# Power.net
KiCad netlist of a schematic drawn in Altium Designer
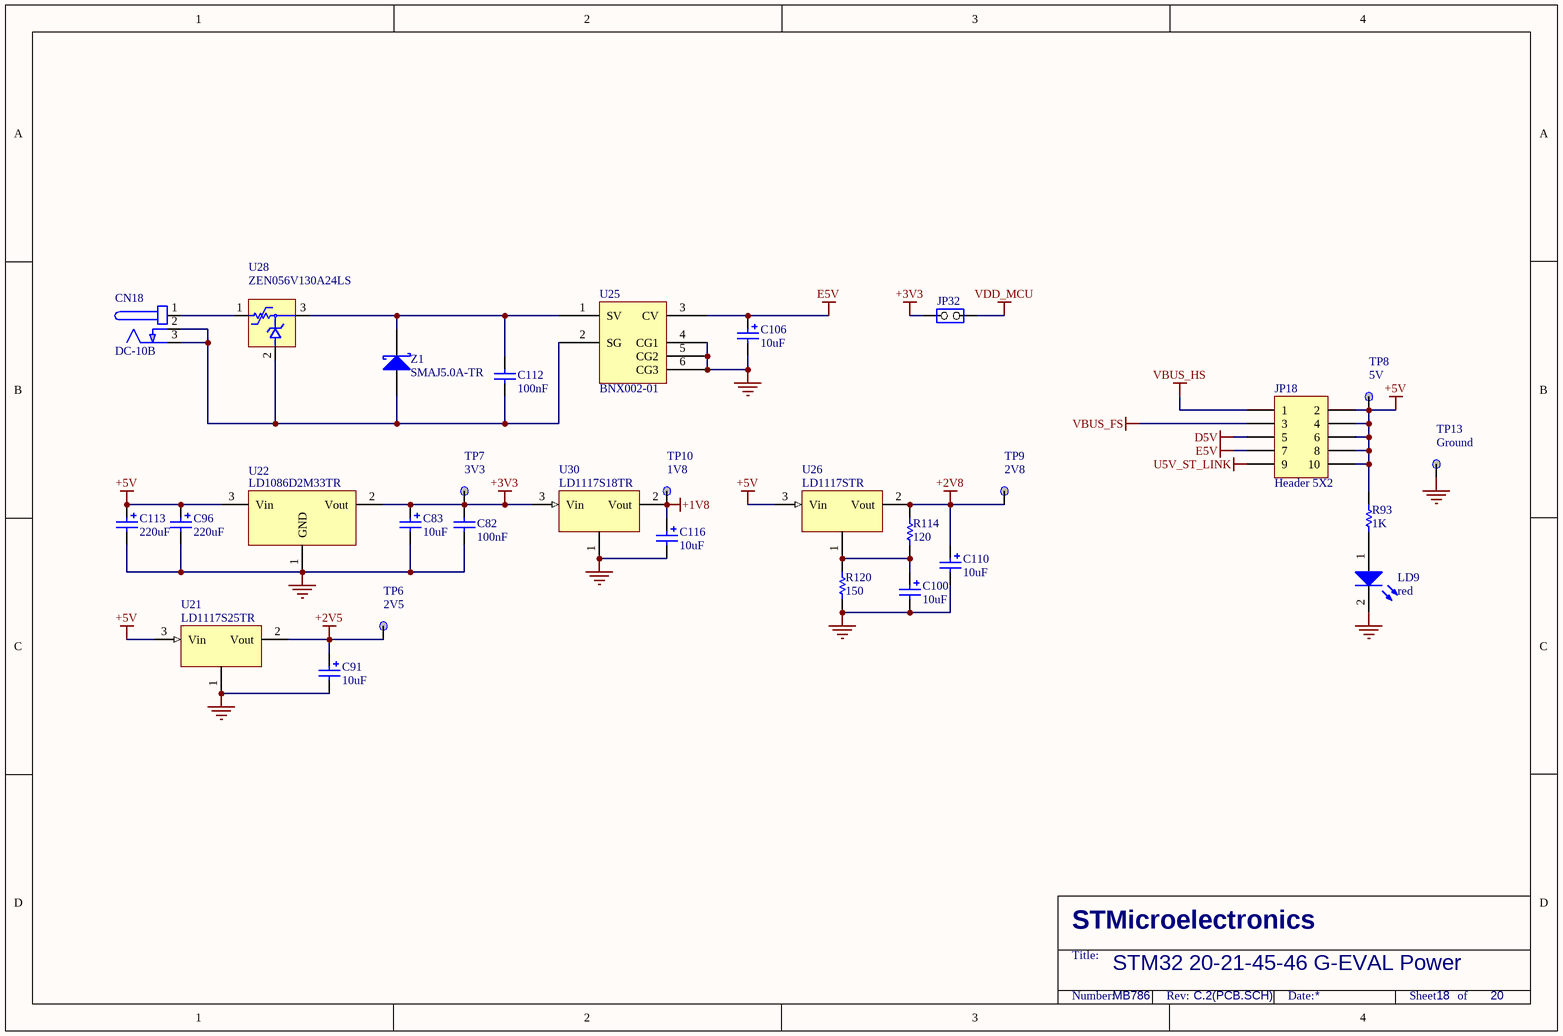
[diagram p0: Power.SchDoc]

(export (version "E")
  (design (tool "Eeschema 10.0.6"))
  (components
    (comp (ref "C82")
      (value "100nF")
      (footprint "0402C")
      (description "Capacitor")
      (fields (field (name "PUBLISHER") "Altium Limited"))
      (libsource (lib "Miscellaneous Devices") (part "Cap"))
    )
    (comp (ref "C83")
      (value "10uF")
      (footprint "TAN-A")
      (description "Polarized Capacitor (Radial)")
      (fields (field (name "PUBLISHER") "Altium Limited"))
      (libsource (lib "Miscellaneous Devices") (part "Cap Pol1"))
    )
    (comp (ref "C91")
      (value "10uF")
      (footprint "TAN-A")
      (description "Polarized Capacitor (Radial)")
      (fields (field (name "PUBLISHER") "Altium Limited"))
      (libsource (lib "Miscellaneous Devices") (part "Cap Pol1"))
    )
    (comp (ref "C96")
      (value "220uF")
      (footprint "C310M-6")
      (description "Polarized Capacitor (Radial)")
      (fields (field (name "PUBLISHER") "Altium Limited"))
      (libsource (lib "Miscellaneous Devices") (part "Cap Pol1"))
    )
    (comp (ref "C100")
      (value "10uF")
      (footprint "TAN-A")
      (description "Polarized Capacitor (Radial)")
      (fields (field (name "PUBLISHER") "Altium Limited"))
      (libsource (lib "Miscellaneous Devices") (part "Cap Pol1"))
    )
    (comp (ref "C106")
      (value "10uF")
      (footprint "C160M-5.5")
      (description "Polarized Capacitor (Radial)")
      (fields (field (name "PUBLISHER") "Altium Limited"))
      (libsource (lib "Miscellaneous Devices") (part "Cap Pol1"))
    )
    (comp (ref "C110")
      (value "10uF")
      (footprint "TAN-A")
      (description "Polarized Capacitor (Radial)")
      (fields (field (name "PUBLISHER") "Altium Limited"))
      (libsource (lib "Miscellaneous Devices") (part "Cap Pol1"))
    )
    (comp (ref "C112")
      (value "100nF")
      (footprint "0402C")
      (description "Capacitor")
      (fields (field (name "PUBLISHER") "Altium Limited"))
      (libsource (lib "Miscellaneous Devices") (part "CAP"))
    )
    (comp (ref "C113")
      (value "220uF")
      (footprint "C310M-6")
      (description "Polarized Capacitor (Radial)")
      (fields (field (name "PUBLISHER") "Altium Limited"))
      (libsource (lib "Miscellaneous Devices") (part "Cap Pol1"))
    )
    (comp (ref "C116")
      (value "10uF")
      (footprint "TAN-A")
      (description "Polarized Capacitor (Radial)")
      (fields (field (name "PUBLISHER") "Altium Limited"))
      (libsource (lib "Miscellaneous Devices") (part "Cap Pol1"))
    )
    (comp (ref "CN18") (value "DC-10B") (footprint "DC10B") (libsource (lib "STR910_SCHLIB") (part "PJ202A")))
    (comp (ref "JP18")
      (value "Header 5X2")
      (footprint "HDR2X5")
      (description "Header, 5-Pin, Dual row")
      (fields (field (name "PUBLISHER") "Altium Limited"))
      (libsource (lib "Miscellaneous Connectors") (part "Header 5X2"))
    )
    (comp (ref "JP32") (value "~") (footprint "SIP2") (libsource (lib "*") (part "JP2")))
    (comp (ref "LD9")
      (value "red")
      (footprint "0603D")
      (description "Typical RED, GREEN, YELLOW, AMBER GaAs LED")
      (fields (field (name "PUBLISHER") "Altium Limited"))
      (libsource (lib "Miscellaneous Devices") (part "LED2"))
    )
    (comp (ref "R93")
      (value "1K")
      (footprint "0603R")
      (description "Resistor")
      (fields (field (name "PUBLISHER") "Altium Limited"))
      (libsource (lib "Miscellaneous Devices") (part "res1"))
    )
    (comp (ref "R114")
      (value "120")
      (footprint "0603R")
      (description "Resistor")
      (fields (field (name "PUBLISHER") "Altium Limited"))
      (libsource (lib "Miscellaneous Devices") (part "res1"))
    )
    (comp (ref "R120")
      (value "150")
      (footprint "0603R")
      (description "Resistor")
      (fields (field (name "PUBLISHER") "Altium Limited"))
      (libsource (lib "Miscellaneous Devices") (part "res1"))
    )
    (comp (ref "TP6") (value "2V5") (footprint "TP") (libsource (lib "*") (part "TP")))
    (comp (ref "TP7") (value "3V3") (footprint "TP") (libsource (lib "*") (part "TP")))
    (comp (ref "TP8") (value "5V") (footprint "TP") (libsource (lib "*") (part "TP")))
    (comp (ref "TP9") (value "2V8") (footprint "TP") (libsource (lib "*") (part "TP")))
    (comp (ref "TP10") (value "1V8") (footprint "TP") (libsource (lib "*") (part "TP")))
    (comp (ref "TP13") (value "Ground") (footprint "TP") (libsource (lib "*") (part "TP")))
    (comp (ref "U21") (value "LD1117S25TR") (footprint "SOT-223") (libsource (lib "*") (part "LD1117")))
    (comp (ref "U22") (value "LD1086D2M33TR") (footprint "D2PAK/A") (libsource (lib "*") (part "VOLTREG1")))
    (comp (ref "U25")
      (value "BNX002-01")
      (footprint "BNX001")
      (libsource (lib "STR910_SCHLIB") (part "BNX002"))
    )
    (comp (ref "U26") (value "LD1117STR") (footprint "SOT-223") (libsource (lib "*") (part "LD1117")))
    (comp (ref "U28")
      (value "ZEN056V130A24LS")
      (footprint "polyzen")
      (libsource (lib "STR910_SCHLIB") (part "ZEN056V130A24LS"))
    )
    (comp (ref "U30") (value "LD1117S18TR") (footprint "SOT-223") (libsource (lib "*") (part "LD1117")))
    (comp (ref "Z1")
      (value "SMAJ5.0A-TR")
      (footprint "1R1C")
      (description "Schottky Diode")
      (fields (field (name "PUBLISHER") "Altium Limited"))
      (libsource (lib "Miscellaneous Devices") (part "D Schottky"))
    )
  )
  (nets
    (net (code "1") (name "+1V8") (class "Default")
      (node (ref "C116") (pin "1") (pinfunction "1_1") (pintype "passive"))
      (node (ref "TP10") (pin "1") (pinfunction "1_1") (pintype "passive"))
      (node (ref "U30") (pin "2") (pinfunction "Vout_2") (pintype "power_in"))
    )
    (net (code "2") (name "+2V5") (class "Default")
      (node (ref "C91") (pin "1") (pinfunction "1_1") (pintype "passive"))
      (node (ref "TP6") (pin "1") (pinfunction "1_1") (pintype "passive"))
      (node (ref "U21") (pin "2") (pinfunction "Vout_2") (pintype "power_in"))
    )
    (net (code "3") (name "+2V8") (class "Default")
      (node (ref "C110") (pin "1") (pinfunction "1_1") (pintype "passive"))
      (node (ref "R114") (pin "1") (pinfunction "1_1") (pintype "passive"))
      (node (ref "TP9") (pin "1") (pinfunction "1_1") (pintype "passive"))
      (node (ref "U26") (pin "2") (pinfunction "Vout_2") (pintype "power_in"))
    )
    (net (code "4") (name "+3V3") (class "Default")
      (node (ref "C82") (pin "1") (pinfunction "1_1") (pintype "passive"))
      (node (ref "C83") (pin "1") (pinfunction "1_1") (pintype "passive"))
      (node (ref "JP32") (pin "1") (pinfunction "COMMON_1") (pintype "passive"))
      (node (ref "TP7") (pin "1") (pinfunction "1_1") (pintype "passive"))
      (node (ref "U22") (pin "2") (pinfunction "Vout_2") (pintype "passive"))
      (node (ref "U30") (pin "3") (pinfunction "Vin_3") (pintype "input"))
    )
    (net (code "5") (name "+5V") (class "Default")
      (node (ref "C113") (pin "1") (pinfunction "1_1") (pintype "passive"))
      (node (ref "C96") (pin "1") (pinfunction "1_1") (pintype "passive"))
      (node (ref "JP18") (pin "10") (pinfunction "10_10") (pintype "passive"))
      (node (ref "JP18") (pin "2") (pinfunction "2_2") (pintype "passive"))
      (node (ref "JP18") (pin "4") (pinfunction "4_4") (pintype "passive"))
      (node (ref "JP18") (pin "6") (pinfunction "6_6") (pintype "passive"))
      (node (ref "JP18") (pin "8") (pinfunction "8_8") (pintype "passive"))
      (node (ref "R93") (pin "2") (pinfunction "2_2") (pintype "passive"))
      (node (ref "TP8") (pin "1") (pinfunction "1_1") (pintype "passive"))
      (node (ref "U21") (pin "3") (pinfunction "Vin_3") (pintype "input"))
      (node (ref "U22") (pin "3") (pinfunction "Vin_3") (pintype "passive"))
      (node (ref "U26") (pin "3") (pinfunction "Vin_3") (pintype "input"))
    )
    (net (code "6") (name "D5V") (class "Default")
      (node (ref "JP18") (pin "5") (pinfunction "5_5") (pintype "passive"))
    )
    (net (code "7") (name "E5V") (class "Default")
      (node (ref "C106") (pin "1") (pinfunction "1_1") (pintype "passive"))
      (node (ref "JP18") (pin "7") (pinfunction "7_7") (pintype "passive"))
      (node (ref "U25") (pin "3") (pinfunction "CV_3") (pintype "passive"))
    )
    (net (code "8") (name "GND") (class "Default")
      (node (ref "C100") (pin "2") (pinfunction "2_2") (pintype "passive"))
      (node (ref "C106") (pin "2") (pinfunction "2_2") (pintype "passive"))
      (node (ref "C110") (pin "2") (pinfunction "2_2") (pintype "passive"))
      (node (ref "C113") (pin "2") (pinfunction "2_2") (pintype "passive"))
      (node (ref "C116") (pin "2") (pinfunction "2_2") (pintype "passive"))
      (node (ref "C82") (pin "2") (pinfunction "2_2") (pintype "passive"))
      (node (ref "C83") (pin "2") (pinfunction "2_2") (pintype "passive"))
      (node (ref "C91") (pin "2") (pinfunction "2_2") (pintype "passive"))
      (node (ref "C96") (pin "2") (pinfunction "2_2") (pintype "passive"))
      (node (ref "LD9") (pin "2") (pinfunction "K_2") (pintype "passive"))
      (node (ref "R120") (pin "2") (pinfunction "2_2") (pintype "passive"))
      (node (ref "TP13") (pin "1") (pinfunction "1_1") (pintype "passive"))
      (node (ref "U21") (pin "1") (pintype "passive"))
      (node (ref "U22") (pin "1") (pinfunction "GND_1") (pintype "passive"))
      (node (ref "U25") (pin "4") (pinfunction "CG1_4") (pintype "passive"))
      (node (ref "U25") (pin "5") (pinfunction "CG2_5") (pintype "passive"))
      (node (ref "U25") (pin "6") (pinfunction "CG3_6") (pintype "passive"))
      (node (ref "U30") (pin "1") (pintype "passive"))
    )
    (net (code "9") (name "Net-(C100-Pad1)") (class "Default")
      (node (ref "C100") (pin "1") (pinfunction "1_1") (pintype "passive"))
      (node (ref "R114") (pin "2") (pinfunction "2_2") (pintype "passive"))
      (node (ref "R120") (pin "1") (pinfunction "1_1") (pintype "passive"))
      (node (ref "U26") (pin "1") (pintype "passive"))
    )
    (net (code "10") (name "Net-(CN18-+)") (class "Default")
      (node (ref "CN18") (pin "1") (pinfunction "+_1") (pintype "passive"))
      (node (ref "U28") (pin "1") (pintype "passive"))
    )
    (net (code "11") (name "Net-(LD9-A)") (class "Default")
      (node (ref "LD9") (pin "1") (pinfunction "A_1") (pintype "passive"))
      (node (ref "R93") (pin "1") (pinfunction "1_1") (pintype "passive"))
    )
    (net (code "12") (name "Net-(U25-SG)") (class "Default")
      (node (ref "C112") (pin "2") (pinfunction "2_2") (pintype "passive"))
      (node (ref "CN18") (pin "2") (pinfunction "GND_2") (pintype "passive"))
      (node (ref "CN18") (pin "3") (pinfunction "GND_3") (pintype "passive"))
      (node (ref "U25") (pin "2") (pinfunction "SG_2") (pintype "passive"))
      (node (ref "U28") (pin "2") (pintype "passive"))
      (node (ref "Z1") (pin "1") (pinfunction "A_1") (pintype "passive"))
    )
    (net (code "13") (name "Net-(U25-SV)") (class "Default")
      (node (ref "C112") (pin "1") (pinfunction "1_1") (pintype "passive"))
      (node (ref "U25") (pin "1") (pinfunction "SV_1") (pintype "passive"))
      (node (ref "U28") (pin "3") (pintype "passive"))
      (node (ref "Z1") (pin "2") (pinfunction "K_2") (pintype "passive"))
    )
    (net (code "14") (name "U5V_ST_LINK") (class "Default")
      (node (ref "JP18") (pin "9") (pinfunction "9_9") (pintype "passive"))
    )
    (net (code "15") (name "VBUS_FS") (class "Default")
      (node (ref "JP18") (pin "3") (pinfunction "3_3") (pintype "passive"))
    )
    (net (code "16") (name "VBUS_HS") (class "Default")
      (node (ref "JP18") (pin "1") (pinfunction "1_1") (pintype "passive"))
    )
    (net (code "17") (name "VDD_MCU") (class "Default")
      (node (ref "JP32") (pin "2") (pinfunction "NO_2") (pintype "passive"))
    )
  )
)
